# BIGDOGLAYOUT2.net
KiCad netlist of a schematic drawn in EAGLE
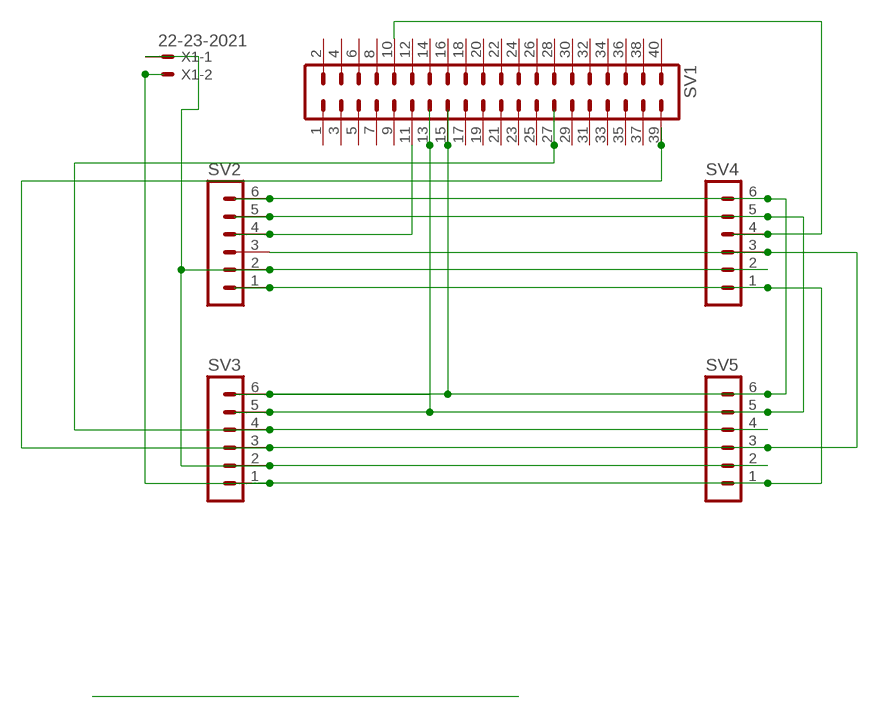
[diagram p0: schematic, sheet 1]

(export (version "E")
  (design (tool "Eeschema 10.0.6"))
  (components
    (comp (ref "SV1")
      (value "MA20-2")
      (footprint "eagle-import:MA20-2")
      (libsource (lib "eagle-import") (part "MA20-2"))
    )
    (comp (ref "SV2")
      (value "MA06-1")
      (footprint "eagle-import:MA06-1")
      (libsource (lib "eagle-import") (part "MA06-1"))
    )
    (comp (ref "SV3")
      (value "MA06-1")
      (footprint "eagle-import:MA06-1")
      (libsource (lib "eagle-import") (part "MA06-1"))
    )
    (comp (ref "SV4")
      (value "MA06-1")
      (footprint "eagle-import:MA06-1")
      (libsource (lib "eagle-import") (part "MA06-1"))
    )
    (comp (ref "SV5")
      (value "MA06-1")
      (footprint "eagle-import:MA06-1")
      (libsource (lib "eagle-import") (part "MA06-1"))
    )
    (comp (ref "X1")
      (value "22-23-2021")
      (footprint "eagle-import:22-23-2021")
      (fields (field (name "MF") "MOLEX"))
      (libsource (lib "eagle-import") (part "22-23-2021"))
    )
  )
  (nets
    (net (code "1") (name "Net-(SV1-Pad10)") (class "Default")
      (node (ref "SV1") (pin "10") (pinfunction "10_10") (pintype "passive"))
      (node (ref "SV4") (pin "4") (pinfunction "4_4") (pintype "passive"))
    )
    (net (code "2") (name "Net-(SV1-Pad11)") (class "Default")
      (node (ref "SV1") (pin "11") (pinfunction "11_11") (pintype "passive"))
      (node (ref "SV2") (pin "4") (pinfunction "4_4") (pintype "passive"))
    )
    (net (code "3") (name "Net-(SV1-Pad13)") (class "Default")
      (node (ref "SV1") (pin "13") (pinfunction "13_13") (pintype "passive"))
      (node (ref "SV2") (pin "5") (pinfunction "5_5") (pintype "passive"))
      (node (ref "SV3") (pin "5") (pinfunction "5_5") (pintype "passive"))
      (node (ref "SV4") (pin "5") (pinfunction "5_5") (pintype "passive"))
      (node (ref "SV5") (pin "5") (pinfunction "5_5") (pintype "passive"))
    )
    (net (code "4") (name "Net-(SV1-Pad15)") (class "Default")
      (node (ref "SV1") (pin "15") (pinfunction "15_15") (pintype "passive"))
      (node (ref "SV2") (pin "6") (pinfunction "6_6") (pintype "passive"))
      (node (ref "SV3") (pin "6") (pinfunction "6_6") (pintype "passive"))
      (node (ref "SV4") (pin "6") (pinfunction "6_6") (pintype "passive"))
      (node (ref "SV5") (pin "6") (pinfunction "6_6") (pintype "passive"))
    )
    (net (code "5") (name "Net-(SV1-Pad27)") (class "Default")
      (node (ref "SV1") (pin "27") (pinfunction "27_27") (pintype "passive"))
      (node (ref "SV3") (pin "4") (pinfunction "4_4") (pintype "passive"))
      (node (ref "SV5") (pin "4") (pinfunction "4_4") (pintype "passive"))
    )
    (net (code "6") (name "Net-(SV1-Pad39)") (class "Default")
      (node (ref "SV1") (pin "39") (pinfunction "39_39") (pintype "passive"))
      (node (ref "SV2") (pin "3") (pinfunction "3_3") (pintype "passive"))
      (node (ref "SV3") (pin "3") (pinfunction "3_3") (pintype "passive"))
      (node (ref "SV4") (pin "3") (pinfunction "3_3") (pintype "passive"))
      (node (ref "SV5") (pin "3") (pinfunction "3_3") (pintype "passive"))
    )
    (net (code "7") (name "Net-(X1A-S)") (class "Default")
      (node (ref "SV2") (pin "2") (pinfunction "2_2") (pintype "passive"))
      (node (ref "SV3") (pin "2") (pinfunction "2_2") (pintype "passive"))
      (node (ref "SV4") (pin "2") (pinfunction "2_2") (pintype "passive"))
      (node (ref "SV5") (pin "2") (pinfunction "2_2") (pintype "passive"))
      (node (ref "X1") (pin "1") (pinfunction "S_1") (pintype "passive"))
    )
    (net (code "8") (name "Net-(X1B-S)") (class "Default")
      (node (ref "SV2") (pin "1") (pinfunction "1_1") (pintype "passive"))
      (node (ref "SV3") (pin "1") (pinfunction "1_1") (pintype "passive"))
      (node (ref "SV4") (pin "1") (pinfunction "1_1") (pintype "passive"))
      (node (ref "SV5") (pin "1") (pinfunction "1_1") (pintype "passive"))
      (node (ref "X1") (pin "2") (pinfunction "S_2") (pintype "passive"))
    )
    (net (code "9") (name "unconnected-(SV1-Pad1)") (class "Default")
      (node (ref "SV1") (pin "1") (pinfunction "1_1") (pintype "passive"))
    )
    (net (code "10") (name "unconnected-(SV1-Pad2)") (class "Default")
      (node (ref "SV1") (pin "2") (pinfunction "2_2") (pintype "passive"))
    )
    (net (code "11") (name "unconnected-(SV1-Pad3)") (class "Default")
      (node (ref "SV1") (pin "3") (pinfunction "3_3") (pintype "passive"))
    )
    (net (code "12") (name "unconnected-(SV1-Pad4)") (class "Default")
      (node (ref "SV1") (pin "4") (pinfunction "4_4") (pintype "passive"))
    )
    (net (code "13") (name "unconnected-(SV1-Pad5)") (class "Default")
      (node (ref "SV1") (pin "5") (pinfunction "5_5") (pintype "passive"))
    )
    (net (code "14") (name "unconnected-(SV1-Pad6)") (class "Default")
      (node (ref "SV1") (pin "6") (pinfunction "6_6") (pintype "passive"))
    )
    (net (code "15") (name "unconnected-(SV1-Pad7)") (class "Default")
      (node (ref "SV1") (pin "7") (pinfunction "7_7") (pintype "passive"))
    )
    (net (code "16") (name "unconnected-(SV1-Pad8)") (class "Default")
      (node (ref "SV1") (pin "8") (pinfunction "8_8") (pintype "passive"))
    )
    (net (code "17") (name "unconnected-(SV1-Pad9)") (class "Default")
      (node (ref "SV1") (pin "9") (pinfunction "9_9") (pintype "passive"))
    )
    (net (code "18") (name "unconnected-(SV1-Pad12)") (class "Default")
      (node (ref "SV1") (pin "12") (pinfunction "12_12") (pintype "passive"))
    )
    (net (code "19") (name "unconnected-(SV1-Pad14)") (class "Default")
      (node (ref "SV1") (pin "14") (pinfunction "14_14") (pintype "passive"))
    )
    (net (code "20") (name "unconnected-(SV1-Pad16)") (class "Default")
      (node (ref "SV1") (pin "16") (pinfunction "16_16") (pintype "passive"))
    )
    (net (code "21") (name "unconnected-(SV1-Pad17)") (class "Default")
      (node (ref "SV1") (pin "17") (pinfunction "17_17") (pintype "passive"))
    )
    (net (code "22") (name "unconnected-(SV1-Pad18)") (class "Default")
      (node (ref "SV1") (pin "18") (pinfunction "18_18") (pintype "passive"))
    )
    (net (code "23") (name "unconnected-(SV1-Pad19)") (class "Default")
      (node (ref "SV1") (pin "19") (pinfunction "19_19") (pintype "passive"))
    )
    (net (code "24") (name "unconnected-(SV1-Pad20)") (class "Default")
      (node (ref "SV1") (pin "20") (pinfunction "20_20") (pintype "passive"))
    )
    (net (code "25") (name "unconnected-(SV1-Pad21)") (class "Default")
      (node (ref "SV1") (pin "21") (pinfunction "21_21") (pintype "passive"))
    )
    (net (code "26") (name "unconnected-(SV1-Pad22)") (class "Default")
      (node (ref "SV1") (pin "22") (pinfunction "22_22") (pintype "passive"))
    )
    (net (code "27") (name "unconnected-(SV1-Pad23)") (class "Default")
      (node (ref "SV1") (pin "23") (pinfunction "23_23") (pintype "passive"))
    )
    (net (code "28") (name "unconnected-(SV1-Pad24)") (class "Default")
      (node (ref "SV1") (pin "24") (pinfunction "24_24") (pintype "passive"))
    )
    (net (code "29") (name "unconnected-(SV1-Pad25)") (class "Default")
      (node (ref "SV1") (pin "25") (pinfunction "25_25") (pintype "passive"))
    )
    (net (code "30") (name "unconnected-(SV1-Pad26)") (class "Default")
      (node (ref "SV1") (pin "26") (pinfunction "26_26") (pintype "passive"))
    )
    (net (code "31") (name "unconnected-(SV1-Pad28)") (class "Default")
      (node (ref "SV1") (pin "28") (pinfunction "28_28") (pintype "passive"))
    )
    (net (code "32") (name "unconnected-(SV1-Pad29)") (class "Default")
      (node (ref "SV1") (pin "29") (pinfunction "29_29") (pintype "passive"))
    )
    (net (code "33") (name "unconnected-(SV1-Pad30)") (class "Default")
      (node (ref "SV1") (pin "30") (pinfunction "30_30") (pintype "passive"))
    )
    (net (code "34") (name "unconnected-(SV1-Pad31)") (class "Default")
      (node (ref "SV1") (pin "31") (pinfunction "31_31") (pintype "passive"))
    )
    (net (code "35") (name "unconnected-(SV1-Pad32)") (class "Default")
      (node (ref "SV1") (pin "32") (pinfunction "32_32") (pintype "passive"))
    )
    (net (code "36") (name "unconnected-(SV1-Pad33)") (class "Default")
      (node (ref "SV1") (pin "33") (pinfunction "33_33") (pintype "passive"))
    )
    (net (code "37") (name "unconnected-(SV1-Pad34)") (class "Default")
      (node (ref "SV1") (pin "34") (pinfunction "34_34") (pintype "passive"))
    )
    (net (code "38") (name "unconnected-(SV1-Pad35)") (class "Default")
      (node (ref "SV1") (pin "35") (pinfunction "35_35") (pintype "passive"))
    )
    (net (code "39") (name "unconnected-(SV1-Pad36)") (class "Default")
      (node (ref "SV1") (pin "36") (pinfunction "36_36") (pintype "passive"))
    )
    (net (code "40") (name "unconnected-(SV1-Pad37)") (class "Default")
      (node (ref "SV1") (pin "37") (pinfunction "37_37") (pintype "passive"))
    )
    (net (code "41") (name "unconnected-(SV1-Pad38)") (class "Default")
      (node (ref "SV1") (pin "38") (pinfunction "38_38") (pintype "passive"))
    )
    (net (code "42") (name "unconnected-(SV1-Pad40)") (class "Default")
      (node (ref "SV1") (pin "40") (pinfunction "40_40") (pintype "passive"))
    )
  )
)
